# joysticks.net
KiCad netlist of a schematic drawn in EAGLE
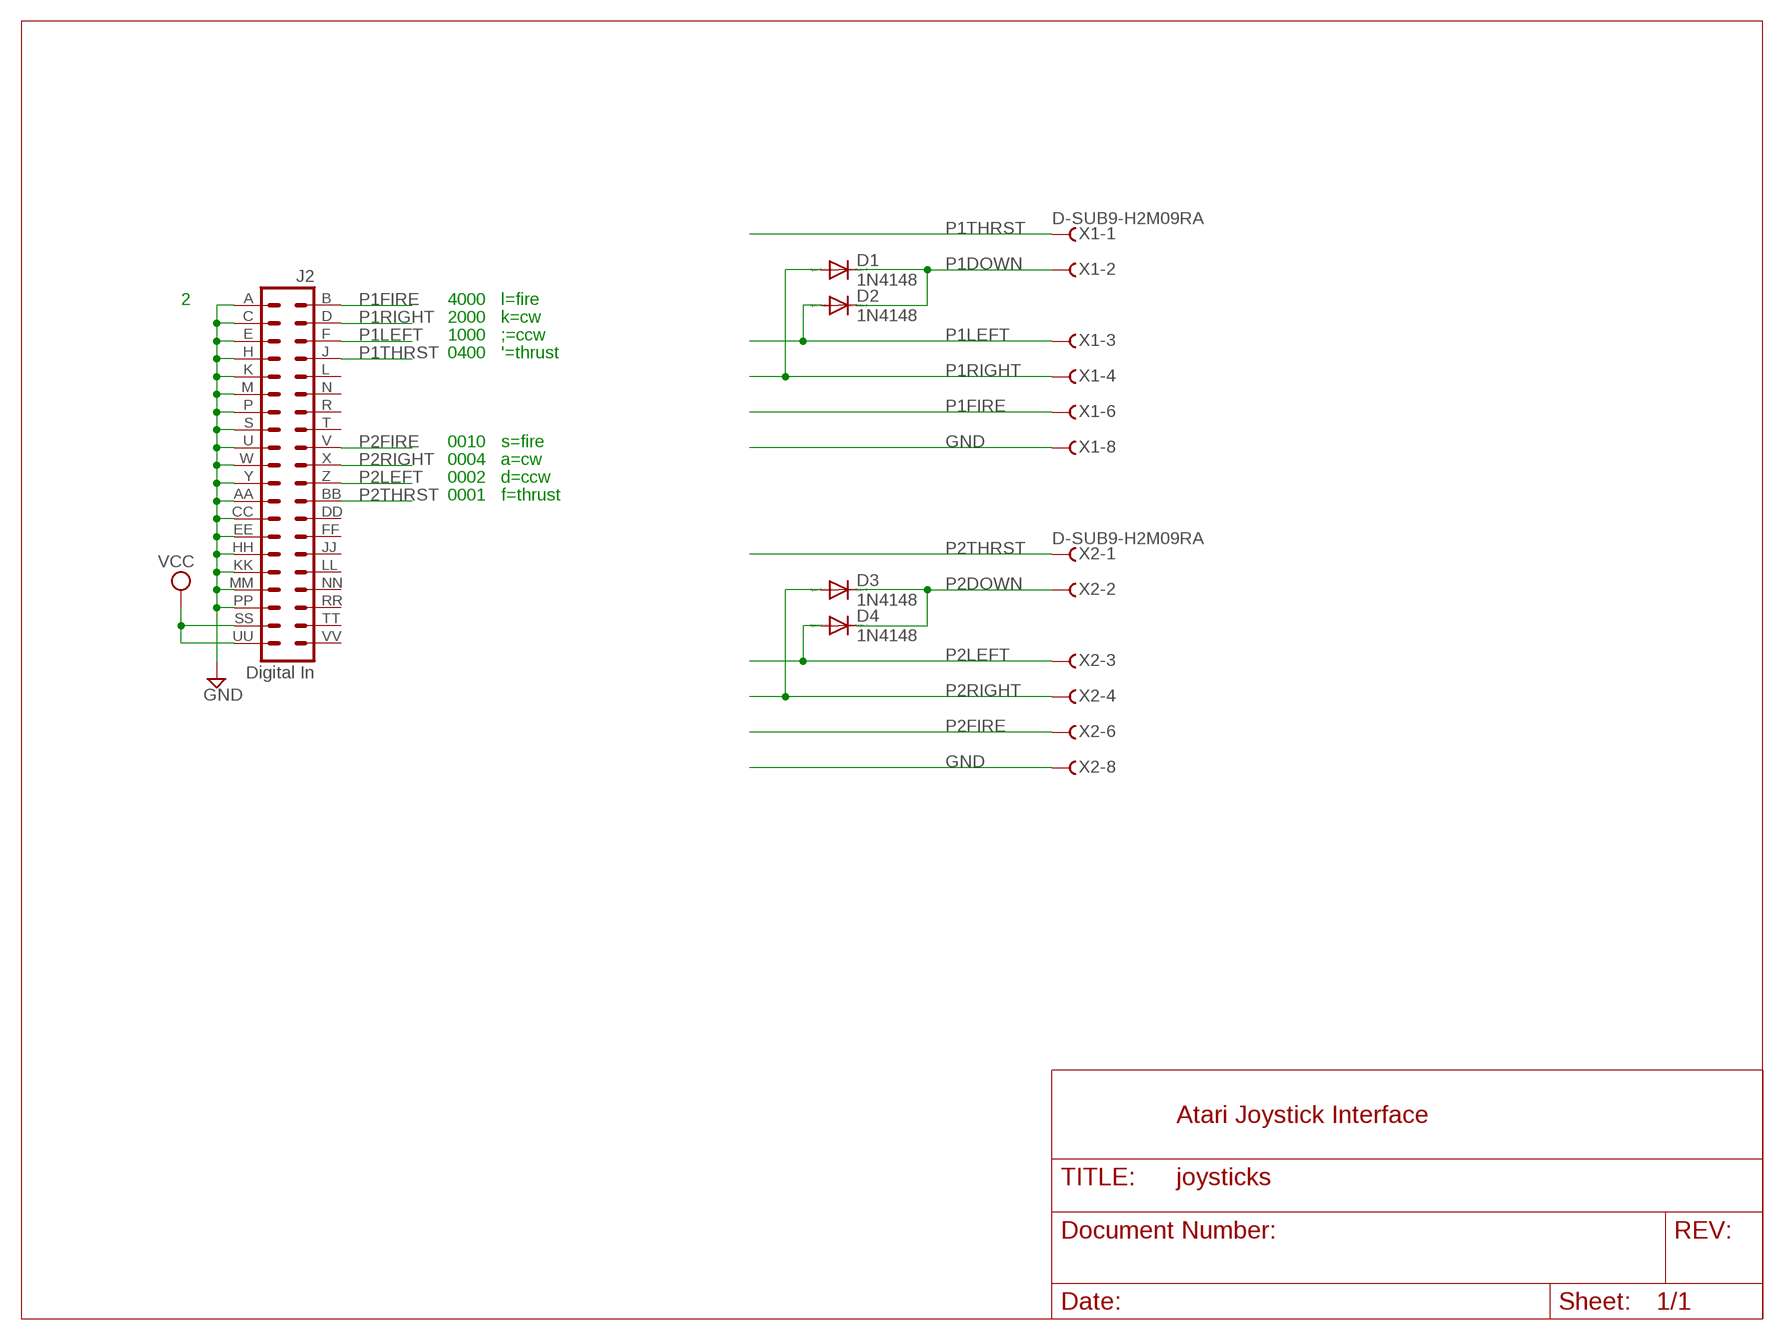
[diagram p0: schematic, sheet 1]

(export (version "E")
  (design (tool "Eeschema 10.0.6"))
  (components
    (comp (ref "D1")
      (value "1N4148")
      (footprint "eagle-import:DO35-10")
      (libsource (lib "eagle-import") (part "DIODE-DO35-10"))
    )
    (comp (ref "D2")
      (value "1N4148")
      (footprint "eagle-import:DO35-10")
      (libsource (lib "eagle-import") (part "DIODE-DO35-10"))
    )
    (comp (ref "D3")
      (value "1N4148")
      (footprint "eagle-import:DO35-10")
      (libsource (lib "eagle-import") (part "DIODE-DO35-10"))
    )
    (comp (ref "D4")
      (value "1N4148")
      (footprint "eagle-import:DO35-10")
      (libsource (lib "eagle-import") (part "DIODE-DO35-10"))
    )
    (comp (ref "J2")
      (value "Digital In")
      (footprint "eagle-import:DEC40PINH")
      (libsource (lib "eagle-import") (part "DEC40PINH"))
    )
    (comp (ref "X1")
      (value "D-SUB9-H2M09RA")
      (footprint "eagle-import:H2M09RA")
      (libsource (lib "eagle-import") (part "D-SUB9-H2M09RA"))
    )
    (comp (ref "X2")
      (value "D-SUB9-H2M09RA")
      (footprint "eagle-import:H2M09RA")
      (libsource (lib "eagle-import") (part "D-SUB9-H2M09RA"))
    )
  )
  (nets
    (net (code "1") (name "/P1DOWN") (class "Default")
      (node (ref "D1") (pin "C") (pinfunction "C_C") (pintype "passive"))
      (node (ref "D2") (pin "C") (pinfunction "C_C") (pintype "passive"))
      (node (ref "X1") (pin "2") (pinfunction "F_2") (pintype "passive"))
    )
    (net (code "2") (name "/P1FIRE") (class "Default")
      (node (ref "J2") (pin "B") (pinfunction "2_B") (pintype "bidirectional"))
      (node (ref "X1") (pin "6") (pinfunction "F_6") (pintype "passive"))
    )
    (net (code "3") (name "/P1LEFT") (class "Default")
      (node (ref "D2") (pin "A") (pinfunction "A_A") (pintype "passive"))
      (node (ref "J2") (pin "F") (pinfunction "6_F") (pintype "bidirectional"))
      (node (ref "X1") (pin "3") (pinfunction "F_3") (pintype "passive"))
    )
    (net (code "4") (name "/P1RIGHT") (class "Default")
      (node (ref "D1") (pin "A") (pinfunction "A_A") (pintype "passive"))
      (node (ref "J2") (pin "D") (pinfunction "4_D") (pintype "bidirectional"))
      (node (ref "X1") (pin "4") (pinfunction "F_4") (pintype "passive"))
    )
    (net (code "5") (name "/P1THRST") (class "Default")
      (node (ref "J2") (pin "J") (pinfunction "8_J") (pintype "bidirectional"))
      (node (ref "X1") (pin "1") (pinfunction "F_1") (pintype "passive"))
    )
    (net (code "6") (name "/P2DOWN") (class "Default")
      (node (ref "D3") (pin "C") (pinfunction "C_C") (pintype "passive"))
      (node (ref "D4") (pin "C") (pinfunction "C_C") (pintype "passive"))
      (node (ref "X2") (pin "2") (pinfunction "F_2") (pintype "passive"))
    )
    (net (code "7") (name "/P2FIRE") (class "Default")
      (node (ref "J2") (pin "V") (pinfunction "18_V") (pintype "bidirectional"))
      (node (ref "X2") (pin "6") (pinfunction "F_6") (pintype "passive"))
    )
    (net (code "8") (name "/P2LEFT") (class "Default")
      (node (ref "D4") (pin "A") (pinfunction "A_A") (pintype "passive"))
      (node (ref "J2") (pin "Z") (pinfunction "22_Z") (pintype "bidirectional"))
      (node (ref "X2") (pin "3") (pinfunction "F_3") (pintype "passive"))
    )
    (net (code "9") (name "/P2RIGHT") (class "Default")
      (node (ref "D3") (pin "A") (pinfunction "A_A") (pintype "passive"))
      (node (ref "J2") (pin "X") (pinfunction "20_X") (pintype "bidirectional"))
      (node (ref "X2") (pin "4") (pinfunction "F_4") (pintype "passive"))
    )
    (net (code "10") (name "/P2THRST") (class "Default")
      (node (ref "J2") (pin "BB") (pinfunction "24_BB") (pintype "bidirectional"))
      (node (ref "X2") (pin "1") (pinfunction "F_1") (pintype "passive"))
    )
    (net (code "11") (name "GND") (class "Default")
      (node (ref "J2") (pin "A") (pinfunction "1_A") (pintype "bidirectional"))
      (node (ref "J2") (pin "AA") (pinfunction "23_AA") (pintype "bidirectional"))
      (node (ref "J2") (pin "C") (pinfunction "3_C") (pintype "bidirectional"))
      (node (ref "J2") (pin "CC") (pinfunction "25_CC") (pintype "bidirectional"))
      (node (ref "J2") (pin "E") (pinfunction "5_E") (pintype "bidirectional"))
      (node (ref "J2") (pin "EE") (pinfunction "27_EE") (pintype "bidirectional"))
      (node (ref "J2") (pin "H") (pinfunction "7_H") (pintype "bidirectional"))
      (node (ref "J2") (pin "HH") (pinfunction "29_HH") (pintype "bidirectional"))
      (node (ref "J2") (pin "K") (pinfunction "9_K") (pintype "bidirectional"))
      (node (ref "J2") (pin "KK") (pinfunction "31_KK") (pintype "bidirectional"))
      (node (ref "J2") (pin "M") (pinfunction "11_M") (pintype "bidirectional"))
      (node (ref "J2") (pin "MM") (pinfunction "33_MM") (pintype "bidirectional"))
      (node (ref "J2") (pin "P") (pinfunction "13_P") (pintype "bidirectional"))
      (node (ref "J2") (pin "PP") (pinfunction "35_PP") (pintype "bidirectional"))
      (node (ref "J2") (pin "S") (pinfunction "15_S") (pintype "bidirectional"))
      (node (ref "J2") (pin "U") (pinfunction "17_U") (pintype "bidirectional"))
      (node (ref "J2") (pin "W") (pinfunction "19_W") (pintype "bidirectional"))
      (node (ref "J2") (pin "Y") (pinfunction "21_Y") (pintype "bidirectional"))
      (node (ref "X1") (pin "8") (pinfunction "F_8") (pintype "passive"))
      (node (ref "X2") (pin "8") (pinfunction "F_8") (pintype "passive"))
    )
    (net (code "12") (name "VCC") (class "Default")
      (node (ref "J2") (pin "SS") (pinfunction "37_SS") (pintype "bidirectional"))
      (node (ref "J2") (pin "UU") (pinfunction "39_UU") (pintype "bidirectional"))
    )
    (net (code "13") (name "unconnected-(J2-10-PadL)") (class "Default")
      (node (ref "J2") (pin "L") (pinfunction "10_L") (pintype "bidirectional"))
    )
    (net (code "14") (name "unconnected-(J2-12-PadN)") (class "Default")
      (node (ref "J2") (pin "N") (pinfunction "12_N") (pintype "bidirectional"))
    )
    (net (code "15") (name "unconnected-(J2-14-PadR)") (class "Default")
      (node (ref "J2") (pin "R") (pinfunction "14_R") (pintype "bidirectional"))
    )
    (net (code "16") (name "unconnected-(J2-16-PadT)") (class "Default")
      (node (ref "J2") (pin "T") (pinfunction "16_T") (pintype "bidirectional"))
    )
    (net (code "17") (name "unconnected-(J2-26-PadDD)") (class "Default")
      (node (ref "J2") (pin "DD") (pinfunction "26_DD") (pintype "bidirectional"))
    )
    (net (code "18") (name "unconnected-(J2-28-PadFF)") (class "Default")
      (node (ref "J2") (pin "FF") (pinfunction "28_FF") (pintype "bidirectional"))
    )
    (net (code "19") (name "unconnected-(J2-30-PadJJ)") (class "Default")
      (node (ref "J2") (pin "JJ") (pinfunction "30_JJ") (pintype "bidirectional"))
    )
    (net (code "20") (name "unconnected-(J2-32-PadLL)") (class "Default")
      (node (ref "J2") (pin "LL") (pinfunction "32_LL") (pintype "bidirectional"))
    )
    (net (code "21") (name "unconnected-(J2-34-PadNN)") (class "Default")
      (node (ref "J2") (pin "NN") (pinfunction "34_NN") (pintype "bidirectional"))
    )
    (net (code "22") (name "unconnected-(J2-36-PadRR)") (class "Default")
      (node (ref "J2") (pin "RR") (pinfunction "36_RR") (pintype "bidirectional"))
    )
    (net (code "23") (name "unconnected-(J2-38-PadTT)") (class "Default")
      (node (ref "J2") (pin "TT") (pinfunction "38_TT") (pintype "bidirectional"))
    )
    (net (code "24") (name "unconnected-(J2-40-PadVV)") (class "Default")
      (node (ref "J2") (pin "VV") (pinfunction "40_VV") (pintype "bidirectional"))
    )
  )
)
